# buck-boost-converter.net
KiCad netlist of a schematic drawn in Altium Designer
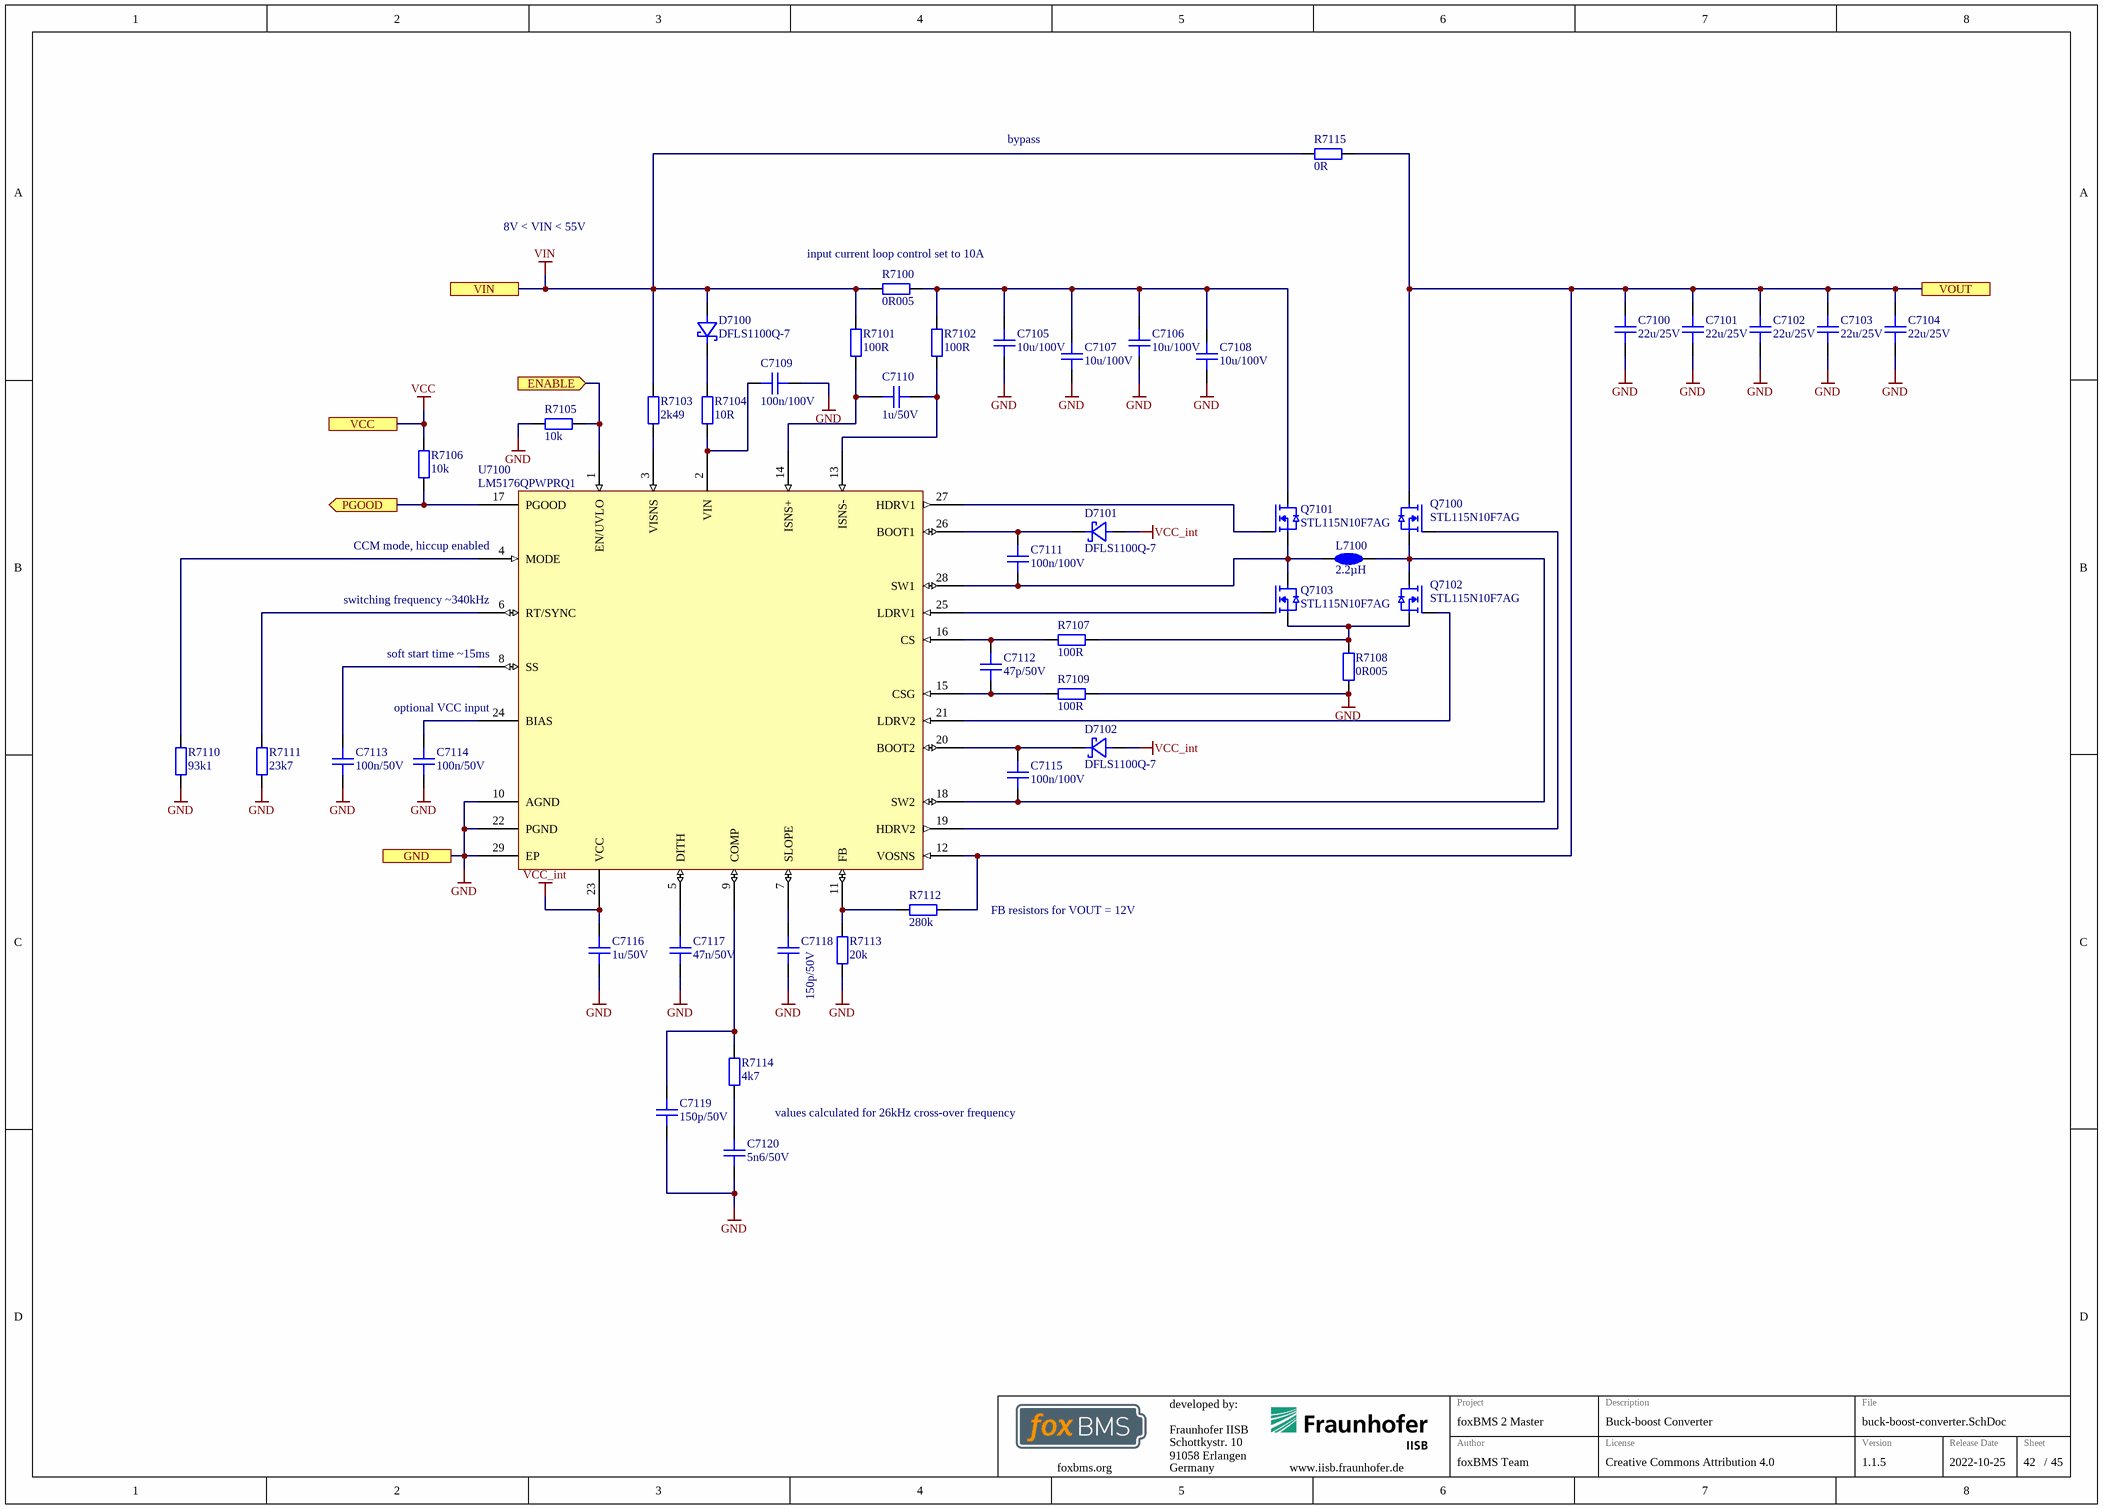
[diagram p0: buck-boost-converter.SchDoc]

(export (version "E")
  (design (tool "Eeschema 10.0.6"))
  (components
    (comp (ref "C7100")
      (value "22u/25V")
      (footprint "CAPC3225X25N")
      (description "MLCC")
      (fields (field (name "PART NUMBER") "gen_C_ceramic_22u_25V_X7R_1210"))
      (libsource (lib "OE750") (part "C"))
    )
    (comp (ref "C7101")
      (value "22u/25V")
      (footprint "CAPC3225X25N")
      (description "MLCC")
      (fields (field (name "PART NUMBER") "gen_C_ceramic_22u_25V_X7R_1210"))
      (libsource (lib "OE750") (part "C"))
    )
    (comp (ref "C7102")
      (value "22u/25V")
      (footprint "CAPC3225X25N")
      (description "MLCC")
      (fields (field (name "PART NUMBER") "gen_C_ceramic_22u_25V_X7R_1210"))
      (libsource (lib "OE750") (part "C"))
    )
    (comp (ref "C7103")
      (value "22u/25V")
      (footprint "CAPC3225X25N")
      (description "MLCC")
      (fields (field (name "PART NUMBER") "gen_C_ceramic_22u_25V_X7R_1210"))
      (libsource (lib "OE750") (part "C"))
    )
    (comp (ref "C7104")
      (value "22u/25V")
      (footprint "CAPC3225X25N")
      (description "MLCC")
      (fields (field (name "PART NUMBER") "gen_C_ceramic_22u_25V_X7R_1210"))
      (libsource (lib "OE750") (part "C"))
    )
    (comp (ref "C7105")
      (value "10u/100V")
      (footprint "CAPC5750X28N")
      (description "MLCC")
      (fields (field (name "PART NUMBER") "gen_C_ceramic_10u_100V_X7S_2220"))
      (libsource (lib "OE750") (part "C"))
    )
    (comp (ref "C7106")
      (value "10u/100V")
      (footprint "CAPC5750X28N")
      (description "MLCC")
      (fields (field (name "PART NUMBER") "gen_C_ceramic_10u_100V_X7S_2220"))
      (libsource (lib "OE750") (part "C"))
    )
    (comp (ref "C7107")
      (value "10u/100V")
      (footprint "CAPC5750X28N")
      (description "MLCC")
      (fields (field (name "PART NUMBER") "gen_C_ceramic_10u_100V_X7S_2220"))
      (libsource (lib "OE750") (part "C"))
    )
    (comp (ref "C7108")
      (value "10u/100V")
      (footprint "CAPC5750X28N")
      (description "MLCC")
      (fields (field (name "PART NUMBER") "gen_C_ceramic_10u_100V_X7S_2220"))
      (libsource (lib "OE750") (part "C"))
    )
    (comp (ref "C7109")
      (value "100n/100V")
      (footprint "CAPC1608X08N")
      (description "MLCC")
      (fields (field (name "PART NUMBER") "gen_C_ceramic_100n_100V_X7R_0603"))
      (libsource (lib "OE750") (part "C"))
    )
    (comp (ref "C7110")
      (value "1u/50V")
      (footprint "CAPC1608X08N")
      (description "MLCC")
      (fields (field (name "PART NUMBER") "gen_C_ceramic_1u_50V_X7R_0603") (field (name "TOLERANCE") "± 10%"))
      (libsource (lib "OE750") (part "C"))
    )
    (comp (ref "C7111")
      (value "100n/100V")
      (footprint "CAPC1608X08N")
      (description "MLCC")
      (fields (field (name "PART NUMBER") "gen_C_ceramic_100n_100V_X7R_0603"))
      (libsource (lib "OE750") (part "C"))
    )
    (comp (ref "C7112")
      (value "47p/50V")
      (footprint "CAPC1005X06N")
      (description "MLCC")
      (fields (field (name "PART NUMBER") "gen_C_ceramic_47p_50V_C0G_0402"))
      (libsource (lib "OE750") (part "C"))
    )
    (comp (ref "C7113")
      (value "100n/50V")
      (footprint "CAPC1005X06N")
      (description "MLCC")
      (fields (field (name "PART NUMBER") "gen_C_ceramic_100n_50V_X7R_0402"))
      (libsource (lib "OE750") (part "C"))
    )
    (comp (ref "C7114")
      (value "100n/50V")
      (footprint "CAPC1005X06N")
      (description "MLCC")
      (fields (field (name "PART NUMBER") "gen_C_ceramic_100n_50V_X7R_0402"))
      (libsource (lib "OE750") (part "C"))
    )
    (comp (ref "C7115")
      (value "100n/100V")
      (footprint "CAPC1608X08N")
      (description "MLCC")
      (fields (field (name "PART NUMBER") "gen_C_ceramic_100n_100V_X7R_0603"))
      (libsource (lib "OE750") (part "C"))
    )
    (comp (ref "C7116")
      (value "1u/50V")
      (footprint "CAPC1608X08N")
      (description "MLCC")
      (fields (field (name "PART NUMBER") "gen_C_ceramic_1u_50V_X7R_0603") (field (name "TOLERANCE") "± 10%"))
      (libsource (lib "OE750") (part "C"))
    )
    (comp (ref "C7117")
      (value "47n/50V")
      (footprint "CAPC1005X06N")
      (description "MLCC")
      (fields (field (name "PART NUMBER") "gen_C_ceramic_47n_50V_X7R_0402"))
      (libsource (lib "OE750") (part "C"))
    )
    (comp (ref "C7118")
      (value "150p/50V")
      (footprint "CAPC1005X06N")
      (description "MLCC")
      (fields (field (name "PART NUMBER") "gen_C_ceramic_150p_50V_C0G_0402"))
      (libsource (lib "OE750") (part "C"))
    )
    (comp (ref "C7119")
      (value "150p/50V")
      (footprint "CAPC1005X06N")
      (description "MLCC")
      (fields (field (name "PART NUMBER") "gen_C_ceramic_150p_50V_C0G_0402"))
      (libsource (lib "OE750") (part "C"))
    )
    (comp (ref "C7120")
      (value "5n6/50V")
      (footprint "CAPC1608X08N")
      (description "MLCC")
      (fields (field (name "PART NUMBER") "gen_C_ceramic_5n6_50V_C0G_0603"))
      (libsource (lib "OE750") (part "C"))
    )
    (comp (ref "D7100")
      (value "DFLS1100Q-7")
      (footprint "PowerDI123")
      (description "Schottky Diode")
      (fields (field (name "MANUFACTURER") "Diodes Inc."))
      (libsource (lib "OE750") (part "D_Schottky"))
    )
    (comp (ref "D7101")
      (value "DFLS1100Q-7")
      (footprint "PowerDI123")
      (description "Schottky Diode")
      (fields (field (name "MANUFACTURER") "Diodes Inc."))
      (libsource (lib "OE750") (part "D_Schottky"))
    )
    (comp (ref "D7102")
      (value "DFLS1100Q-7")
      (footprint "PowerDI123")
      (description "Schottky Diode")
      (fields (field (name "MANUFACTURER") "Diodes Inc."))
      (libsource (lib "OE750") (part "D_Schottky"))
    )
    (comp (ref "L7100")
      (value "2.2µH")
      (footprint "COILCRAFT_XAL1010")
      (description "Power Inductor")
      (fields (field (name "PART NUMBER") "XAL1010-222MEB") (field (name "MANUFACTURER") "Coilcraft"))
      (libsource (lib "OE750") (part "L"))
    )
    (comp (ref "Q7100")
      (value "STL115N10F7AG")
      (footprint "ST_PowerFLAT_5x6_WF_type_C")
      (description "N-Channel MOSFET, 100 V, 107 A, 5 mOhm")
      (fields (field (name "MANUFACTURER") "STMicroelectronics"))
      (libsource (lib "OE750") (part "NMOS"))
    )
    (comp (ref "Q7101")
      (value "STL115N10F7AG")
      (footprint "ST_PowerFLAT_5x6_WF_type_C")
      (description "N-Channel MOSFET, 100 V, 107 A, 5 mOhm")
      (fields (field (name "MANUFACTURER") "STMicroelectronics"))
      (libsource (lib "OE750") (part "NMOS"))
    )
    (comp (ref "Q7102")
      (value "STL115N10F7AG")
      (footprint "ST_PowerFLAT_5x6_WF_type_C")
      (description "N-Channel MOSFET, 100 V, 107 A, 5 mOhm")
      (fields (field (name "MANUFACTURER") "STMicroelectronics"))
      (libsource (lib "OE750") (part "NMOS"))
    )
    (comp (ref "Q7103")
      (value "STL115N10F7AG")
      (footprint "ST_PowerFLAT_5x6_WF_type_C")
      (description "N-Channel MOSFET, 100 V, 107 A, 5 mOhm")
      (fields (field (name "MANUFACTURER") "STMicroelectronics"))
      (libsource (lib "OE750") (part "NMOS"))
    )
    (comp (ref "R7100")
      (value "0R005")
      (footprint "PANASONIC_ERJMS4H")
      (description "SMD Shunt Resistor 0R005")
      (fields (field (name "PART NUMBER") "ERJ-MS4HF5M0U") (field (name "TOLERANCE") "1%"))
      (libsource (lib "OE750") (part "R"))
    )
    (comp (ref "R7101")
      (value "100R")
      (footprint "RESC1005X04N")
      (description "SMD Resistor 100R 0402")
      (fields (field (name "PART NUMBER") "gen_R_100R_0402") (field (name "TOLERANCE") "1%"))
      (libsource (lib "OE750") (part "R"))
    )
    (comp (ref "R7102")
      (value "100R")
      (footprint "RESC1005X04N")
      (description "SMD Resistor 100R 0402")
      (fields (field (name "PART NUMBER") "gen_R_100R_0402") (field (name "TOLERANCE") "1%"))
      (libsource (lib "OE750") (part "R"))
    )
    (comp (ref "R7103")
      (value "2k49")
      (footprint "RESC1005X04N")
      (description "SMD Resistor 2k49 0402")
      (fields (field (name "PART NUMBER") "gen_R_2k49_0402") (field (name "TOLERANCE") "1%"))
      (libsource (lib "OE750") (part "R"))
    )
    (comp (ref "R7104")
      (value "10R")
      (footprint "RESC1005X04N")
      (description "SMD Resistor 10R 0402")
      (fields (field (name "PART NUMBER") "gen_R_10R_0402") (field (name "TOLERANCE") "1%"))
      (libsource (lib "OE750") (part "R"))
    )
    (comp (ref "R7105")
      (value "10k")
      (footprint "RESC1005X04N")
      (description "SMD Resistor 10k 0402")
      (fields (field (name "PART NUMBER") "gen_R_10k_0402") (field (name "TOLERANCE") "1%"))
      (libsource (lib "OE750") (part "R"))
    )
    (comp (ref "R7106")
      (value "10k")
      (footprint "RESC1005X04N")
      (description "SMD Resistor 10k 0402")
      (fields (field (name "PART NUMBER") "gen_R_10k_0402") (field (name "TOLERANCE") "1%"))
      (libsource (lib "OE750") (part "R"))
    )
    (comp (ref "R7107")
      (value "100R")
      (footprint "RESC1005X04N")
      (description "SMD Resistor 100R 0402")
      (fields (field (name "PART NUMBER") "gen_R_100R_0402") (field (name "TOLERANCE") "1%"))
      (libsource (lib "OE750") (part "R"))
    )
    (comp (ref "R7108")
      (value "0R005")
      (footprint "PANASONIC_ERJMS4H")
      (description "SMD Shunt Resistor 0R005")
      (fields (field (name "PART NUMBER") "ERJ-MS4HF5M0U") (field (name "TOLERANCE") "1%"))
      (libsource (lib "OE750") (part "R"))
    )
    (comp (ref "R7109")
      (value "100R")
      (footprint "RESC1005X04N")
      (description "SMD Resistor 100R 0402")
      (fields (field (name "PART NUMBER") "gen_R_100R_0402") (field (name "TOLERANCE") "1%"))
      (libsource (lib "OE750") (part "R"))
    )
    (comp (ref "R7110")
      (value "93k1")
      (footprint "RESC1005X04N")
      (description "SMD Resistor 93k1 0402")
      (fields (field (name "PART NUMBER") "gen_R_93k1_0402") (field (name "TOLERANCE") "1%"))
      (libsource (lib "OE750") (part "R"))
    )
    (comp (ref "R7111")
      (value "23k7")
      (footprint "RESC1005X04N")
      (description "SMD Resistor 23k7 0402")
      (fields (field (name "PART NUMBER") "gen_R_23k7_0402") (field (name "TOLERANCE") "1%"))
      (libsource (lib "OE750") (part "R"))
    )
    (comp (ref "R7112")
      (value "280k")
      (footprint "RESC1005X04N")
      (description "SMD Resistor 280k 0402")
      (fields (field (name "PART NUMBER") "gen_R_280k_0402") (field (name "TOLERANCE") "1%"))
      (libsource (lib "OE750") (part "R"))
    )
    (comp (ref "R7113")
      (value "20k")
      (footprint "RESC1005X04N")
      (description "SMD Resistor 20k 0402")
      (fields (field (name "PART NUMBER") "gen_R_20k_0402") (field (name "TOLERANCE") "1%"))
      (libsource (lib "OE750") (part "R"))
    )
    (comp (ref "R7114")
      (value "4k7")
      (footprint "RESC1005X04N")
      (description "SMD Resistor 4k7 0402")
      (fields (field (name "PART NUMBER") "gen_R_4k7_0402") (field (name "TOLERANCE") "1%"))
      (libsource (lib "OE750") (part "R"))
    )
    (comp (ref "R7115")
      (value "0R")
      (footprint "RESC6331X07N")
      (description "SMD Resistor 0R 2512")
      (fields (field (name "PART NUMBER") "gen_R_0R_2512") (field (name "POWER") "1W"))
      (libsource (lib "OE750") (part "R"))
    )
    (comp (ref "U7100")
      (value "LM5176QPWPRQ1")
      (footprint "LM5176-PWP")
      (description "55-V wide VIN synchronous 4-switch buck-boost controller")
      (fields (field (name "MANUFACTURER") "Texas Instruments"))
      (libsource (lib "OE750") (part "LM5176"))
    )
  )
  (nets
    (net (code "1") (name "/ENABLE") (class "Default")
      (node (ref "R7105") (pin "1") (pinfunction "1_1") (pintype "passive"))
      (node (ref "U7100") (pin "1") (pinfunction "EN/UVLO_1") (pintype "input"))
    )
    (net (code "2") (name "/PGOOD") (class "Default")
      (node (ref "R7106") (pin "1") (pinfunction "1_1") (pintype "passive"))
      (node (ref "U7100") (pin "17") (pinfunction "PGOOD_17") (pintype "open_collector"))
    )
    (net (code "3") (name "/VOUT") (class "Default")
      (node (ref "C7100") (pin "2") (pinfunction "2_2") (pintype "passive"))
      (node (ref "C7101") (pin "2") (pinfunction "2_2") (pintype "passive"))
      (node (ref "C7102") (pin "2") (pinfunction "2_2") (pintype "passive"))
      (node (ref "C7103") (pin "2") (pinfunction "2_2") (pintype "passive"))
      (node (ref "C7104") (pin "2") (pinfunction "2_2") (pintype "passive"))
      (node (ref "Q7100") (pin "D") (pinfunction "D_D") (pintype "passive"))
      (node (ref "R7112") (pin "1") (pinfunction "1_1") (pintype "passive"))
      (node (ref "R7115") (pin "2") (pinfunction "2_2") (pintype "passive"))
      (node (ref "U7100") (pin "12") (pinfunction "VOSNS_12") (pintype "input"))
    )
    (net (code "4") (name "GND") (class "Default")
      (node (ref "C7100") (pin "1") (pinfunction "1_1") (pintype "passive"))
      (node (ref "C7101") (pin "1") (pinfunction "1_1") (pintype "passive"))
      (node (ref "C7102") (pin "1") (pinfunction "1_1") (pintype "passive"))
      (node (ref "C7103") (pin "1") (pinfunction "1_1") (pintype "passive"))
      (node (ref "C7104") (pin "1") (pinfunction "1_1") (pintype "passive"))
      (node (ref "C7105") (pin "1") (pinfunction "1_1") (pintype "passive"))
      (node (ref "C7106") (pin "1") (pinfunction "1_1") (pintype "passive"))
      (node (ref "C7107") (pin "1") (pinfunction "1_1") (pintype "passive"))
      (node (ref "C7108") (pin "1") (pinfunction "1_1") (pintype "passive"))
      (node (ref "C7109") (pin "1") (pinfunction "1_1") (pintype "passive"))
      (node (ref "C7113") (pin "2") (pinfunction "2_2") (pintype "passive"))
      (node (ref "C7114") (pin "2") (pinfunction "2_2") (pintype "passive"))
      (node (ref "C7116") (pin "2") (pinfunction "2_2") (pintype "passive"))
      (node (ref "C7117") (pin "1") (pinfunction "1_1") (pintype "passive"))
      (node (ref "C7118") (pin "1") (pinfunction "1_1") (pintype "passive"))
      (node (ref "C7119") (pin "1") (pinfunction "1_1") (pintype "passive"))
      (node (ref "C7120") (pin "1") (pinfunction "1_1") (pintype "passive"))
      (node (ref "R7105") (pin "2") (pinfunction "2_2") (pintype "passive"))
      (node (ref "R7108") (pin "1") (pinfunction "1_1") (pintype "passive"))
      (node (ref "R7109") (pin "1") (pinfunction "1_1") (pintype "passive"))
      (node (ref "R7110") (pin "1") (pinfunction "1_1") (pintype "passive"))
      (node (ref "R7111") (pin "1") (pinfunction "1_1") (pintype "passive"))
      (node (ref "R7113") (pin "1") (pinfunction "1_1") (pintype "passive"))
      (node (ref "U7100") (pin "10") (pinfunction "AGND_10") (pintype "power_in"))
      (node (ref "U7100") (pin "22") (pinfunction "PGND_22") (pintype "power_in"))
      (node (ref "U7100") (pin "29") (pinfunction "EP_29") (pintype "power_in"))
    )
    (net (code "5") (name "Net-(C7105-Pad2)") (class "Default")
      (node (ref "C7105") (pin "2") (pinfunction "2_2") (pintype "passive"))
      (node (ref "C7106") (pin "2") (pinfunction "2_2") (pintype "passive"))
      (node (ref "C7107") (pin "2") (pinfunction "2_2") (pintype "passive"))
      (node (ref "C7108") (pin "2") (pinfunction "2_2") (pintype "passive"))
      (node (ref "Q7101") (pin "D") (pinfunction "D_D") (pintype "passive"))
      (node (ref "R7100") (pin "2") (pinfunction "2_2") (pintype "passive"))
      (node (ref "R7102") (pin "2") (pinfunction "2_2") (pintype "passive"))
    )
    (net (code "6") (name "Net-(C7120-Pad2)") (class "Default")
      (node (ref "C7120") (pin "2") (pinfunction "2_2") (pintype "passive"))
      (node (ref "R7114") (pin "1") (pinfunction "1_1") (pintype "passive"))
    )
    (net (code "7") (name "Net-(D7100-K)") (class "Default")
      (node (ref "D7100") (pin "1") (pinfunction "K_1") (pintype "passive"))
      (node (ref "R7104") (pin "2") (pinfunction "2_2") (pintype "passive"))
    )
    (net (code "8") (name "Net-(D7101-K)") (class "Default")
      (node (ref "C7111") (pin "1") (pinfunction "1_1") (pintype "passive"))
      (node (ref "D7101") (pin "1") (pinfunction "K_1") (pintype "passive"))
      (node (ref "U7100") (pin "26") (pinfunction "BOOT1_26") (pintype "bidirectional"))
    )
    (net (code "9") (name "Net-(D7102-K)") (class "Default")
      (node (ref "C7115") (pin "1") (pinfunction "1_1") (pintype "passive"))
      (node (ref "D7102") (pin "1") (pinfunction "K_1") (pintype "passive"))
      (node (ref "U7100") (pin "20") (pinfunction "BOOT2_20") (pintype "bidirectional"))
    )
    (net (code "10") (name "Net-(Q7102-PadS)") (class "Default")
      (node (ref "Q7102") (pin "S") (pinfunction "S_S") (pintype "passive"))
      (node (ref "Q7103") (pin "S") (pinfunction "S_S") (pintype "passive"))
      (node (ref "R7107") (pin "1") (pinfunction "1_1") (pintype "passive"))
      (node (ref "R7108") (pin "2") (pinfunction "2_2") (pintype "passive"))
    )
    (net (code "11") (name "Net-(U7100-BIAS)") (class "Default")
      (node (ref "C7114") (pin "1") (pinfunction "1_1") (pintype "passive"))
      (node (ref "U7100") (pin "24") (pinfunction "BIAS_24") (pintype "power_in"))
    )
    (net (code "12") (name "Net-(U7100-COMP)") (class "Default")
      (node (ref "C7119") (pin "2") (pinfunction "2_2") (pintype "passive"))
      (node (ref "R7114") (pin "2") (pinfunction "2_2") (pintype "passive"))
      (node (ref "U7100") (pin "9") (pinfunction "COMP_9") (pintype "bidirectional"))
    )
    (net (code "13") (name "Net-(U7100-CS)") (class "Default")
      (node (ref "C7112") (pin "2") (pinfunction "2_2") (pintype "passive"))
      (node (ref "R7107") (pin "2") (pinfunction "2_2") (pintype "passive"))
      (node (ref "U7100") (pin "16") (pinfunction "CS_16") (pintype "input"))
    )
    (net (code "14") (name "Net-(U7100-CSG)") (class "Default")
      (node (ref "C7112") (pin "1") (pinfunction "1_1") (pintype "passive"))
      (node (ref "R7109") (pin "2") (pinfunction "2_2") (pintype "passive"))
      (node (ref "U7100") (pin "15") (pinfunction "CSG_15") (pintype "input"))
    )
    (net (code "15") (name "Net-(U7100-DITH)") (class "Default")
      (node (ref "C7117") (pin "2") (pinfunction "2_2") (pintype "passive"))
      (node (ref "U7100") (pin "5") (pinfunction "DITH_5") (pintype "bidirectional"))
    )
    (net (code "16") (name "Net-(U7100-FB)") (class "Default")
      (node (ref "R7112") (pin "2") (pinfunction "2_2") (pintype "passive"))
      (node (ref "R7113") (pin "2") (pinfunction "2_2") (pintype "passive"))
      (node (ref "U7100") (pin "11") (pinfunction "FB_11") (pintype "bidirectional"))
    )
    (net (code "17") (name "Net-(U7100-HDRV1)") (class "Default")
      (node (ref "Q7101") (pin "G") (pinfunction "G_G") (pintype "passive"))
      (node (ref "U7100") (pin "27") (pinfunction "HDRV1_27") (pintype "output"))
    )
    (net (code "18") (name "Net-(U7100-HDRV2)") (class "Default")
      (node (ref "Q7100") (pin "G") (pinfunction "G_G") (pintype "passive"))
      (node (ref "U7100") (pin "19") (pinfunction "HDRV2_19") (pintype "output"))
    )
    (net (code "19") (name "Net-(U7100-ISNS+)") (class "Default")
      (node (ref "C7110") (pin "2") (pinfunction "2_2") (pintype "passive"))
      (node (ref "R7101") (pin "1") (pinfunction "1_1") (pintype "passive"))
      (node (ref "U7100") (pin "14") (pinfunction "ISNS+_14") (pintype "input"))
    )
    (net (code "20") (name "Net-(U7100-ISNS-)") (class "Default")
      (node (ref "C7110") (pin "1") (pinfunction "1_1") (pintype "passive"))
      (node (ref "R7102") (pin "1") (pinfunction "1_1") (pintype "passive"))
      (node (ref "U7100") (pin "13") (pinfunction "ISNS-_13") (pintype "input"))
    )
    (net (code "21") (name "Net-(U7100-LDRV1)") (class "Default")
      (node (ref "Q7103") (pin "G") (pinfunction "G_G") (pintype "passive"))
      (node (ref "U7100") (pin "25") (pinfunction "LDRV1_25") (pintype "input"))
    )
    (net (code "22") (name "Net-(U7100-LDRV2)") (class "Default")
      (node (ref "Q7102") (pin "G") (pinfunction "G_G") (pintype "passive"))
      (node (ref "U7100") (pin "21") (pinfunction "LDRV2_21") (pintype "input"))
    )
    (net (code "23") (name "Net-(U7100-MODE)") (class "Default")
      (node (ref "R7110") (pin "2") (pinfunction "2_2") (pintype "passive"))
      (node (ref "U7100") (pin "4") (pinfunction "MODE_4") (pintype "input"))
    )
    (net (code "24") (name "Net-(U7100-RT{slash}SYNC)") (class "Default")
      (node (ref "R7111") (pin "2") (pinfunction "2_2") (pintype "passive"))
      (node (ref "U7100") (pin "6") (pinfunction "RT/SYNC_6") (pintype "bidirectional"))
    )
    (net (code "25") (name "Net-(U7100-SLOPE)") (class "Default")
      (node (ref "C7118") (pin "2") (pinfunction "2_2") (pintype "passive"))
      (node (ref "U7100") (pin "7") (pinfunction "SLOPE_7") (pintype "bidirectional"))
    )
    (net (code "26") (name "Net-(U7100-SS)") (class "Default")
      (node (ref "C7113") (pin "1") (pinfunction "1_1") (pintype "passive"))
      (node (ref "U7100") (pin "8") (pinfunction "SS_8") (pintype "bidirectional"))
    )
    (net (code "27") (name "Net-(U7100-SW1)") (class "Default")
      (node (ref "C7111") (pin "2") (pinfunction "2_2") (pintype "passive"))
      (node (ref "L7100") (pin "1") (pinfunction "1_1") (pintype "passive"))
      (node (ref "Q7101") (pin "S") (pinfunction "S_S") (pintype "passive"))
      (node (ref "Q7103") (pin "D") (pinfunction "D_D") (pintype "passive"))
      (node (ref "U7100") (pin "28") (pinfunction "SW1_28") (pintype "bidirectional"))
    )
    (net (code "28") (name "Net-(U7100-SW2)") (class "Default")
      (node (ref "C7115") (pin "2") (pinfunction "2_2") (pintype "passive"))
      (node (ref "L7100") (pin "2") (pinfunction "2_2") (pintype "passive"))
      (node (ref "Q7100") (pin "S") (pinfunction "S_S") (pintype "passive"))
      (node (ref "Q7102") (pin "D") (pinfunction "D_D") (pintype "passive"))
      (node (ref "U7100") (pin "18") (pinfunction "SW2_18") (pintype "bidirectional"))
    )
    (net (code "29") (name "Net-(U7100-VIN)") (class "Default")
      (node (ref "C7109") (pin "2") (pinfunction "2_2") (pintype "passive"))
      (node (ref "R7104") (pin "1") (pinfunction "1_1") (pintype "passive"))
      (node (ref "U7100") (pin "2") (pinfunction "VIN_2") (pintype "power_in"))
    )
    (net (code "30") (name "Net-(U7100-VISNS)") (class "Default")
      (node (ref "R7103") (pin "1") (pinfunction "1_1") (pintype "passive"))
      (node (ref "U7100") (pin "3") (pinfunction "VISNS_3") (pintype "input"))
    )
    (net (code "31") (name "VCC") (class "Default")
      (node (ref "R7106") (pin "2") (pinfunction "2_2") (pintype "passive"))
    )
    (net (code "32") (name "VCC_int") (class "Default")
      (node (ref "C7116") (pin "1") (pinfunction "1_1") (pintype "passive"))
      (node (ref "D7101") (pin "2") (pinfunction "A_2") (pintype "passive"))
      (node (ref "D7102") (pin "2") (pinfunction "A_2") (pintype "passive"))
      (node (ref "U7100") (pin "23") (pinfunction "VCC_23") (pintype "power_in"))
    )
    (net (code "33") (name "VIN") (class "Default")
      (node (ref "D7100") (pin "2") (pinfunction "A_2") (pintype "passive"))
      (node (ref "R7100") (pin "1") (pinfunction "1_1") (pintype "passive"))
      (node (ref "R7101") (pin "2") (pinfunction "2_2") (pintype "passive"))
      (node (ref "R7103") (pin "2") (pinfunction "2_2") (pintype "passive"))
      (node (ref "R7115") (pin "1") (pinfunction "1_1") (pintype "passive"))
    )
  )
)
